# auxDaqUnitBottom2022.net
KiCad netlist of a schematic drawn in EAGLE
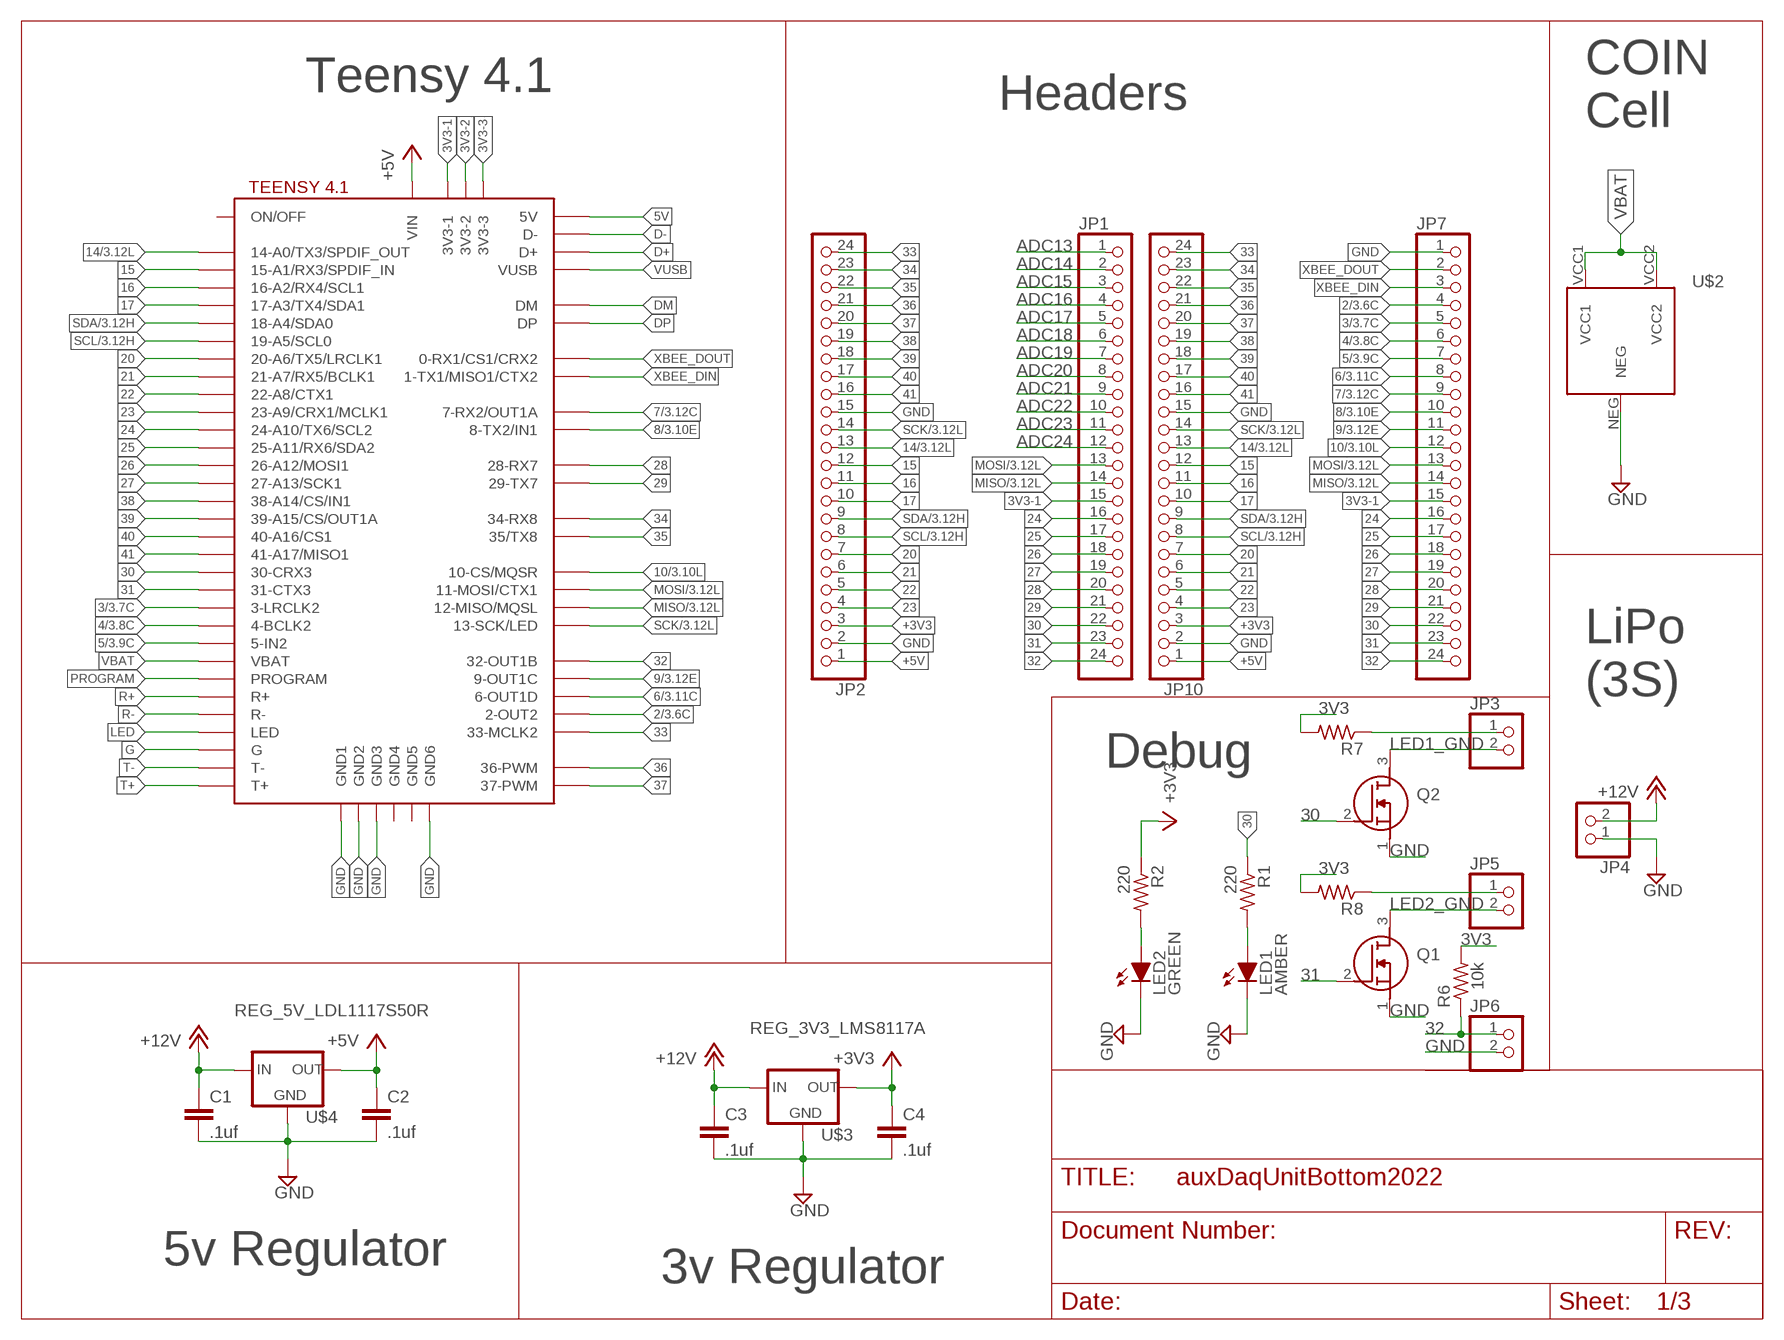
[diagram p0: schematic, sheet 1]
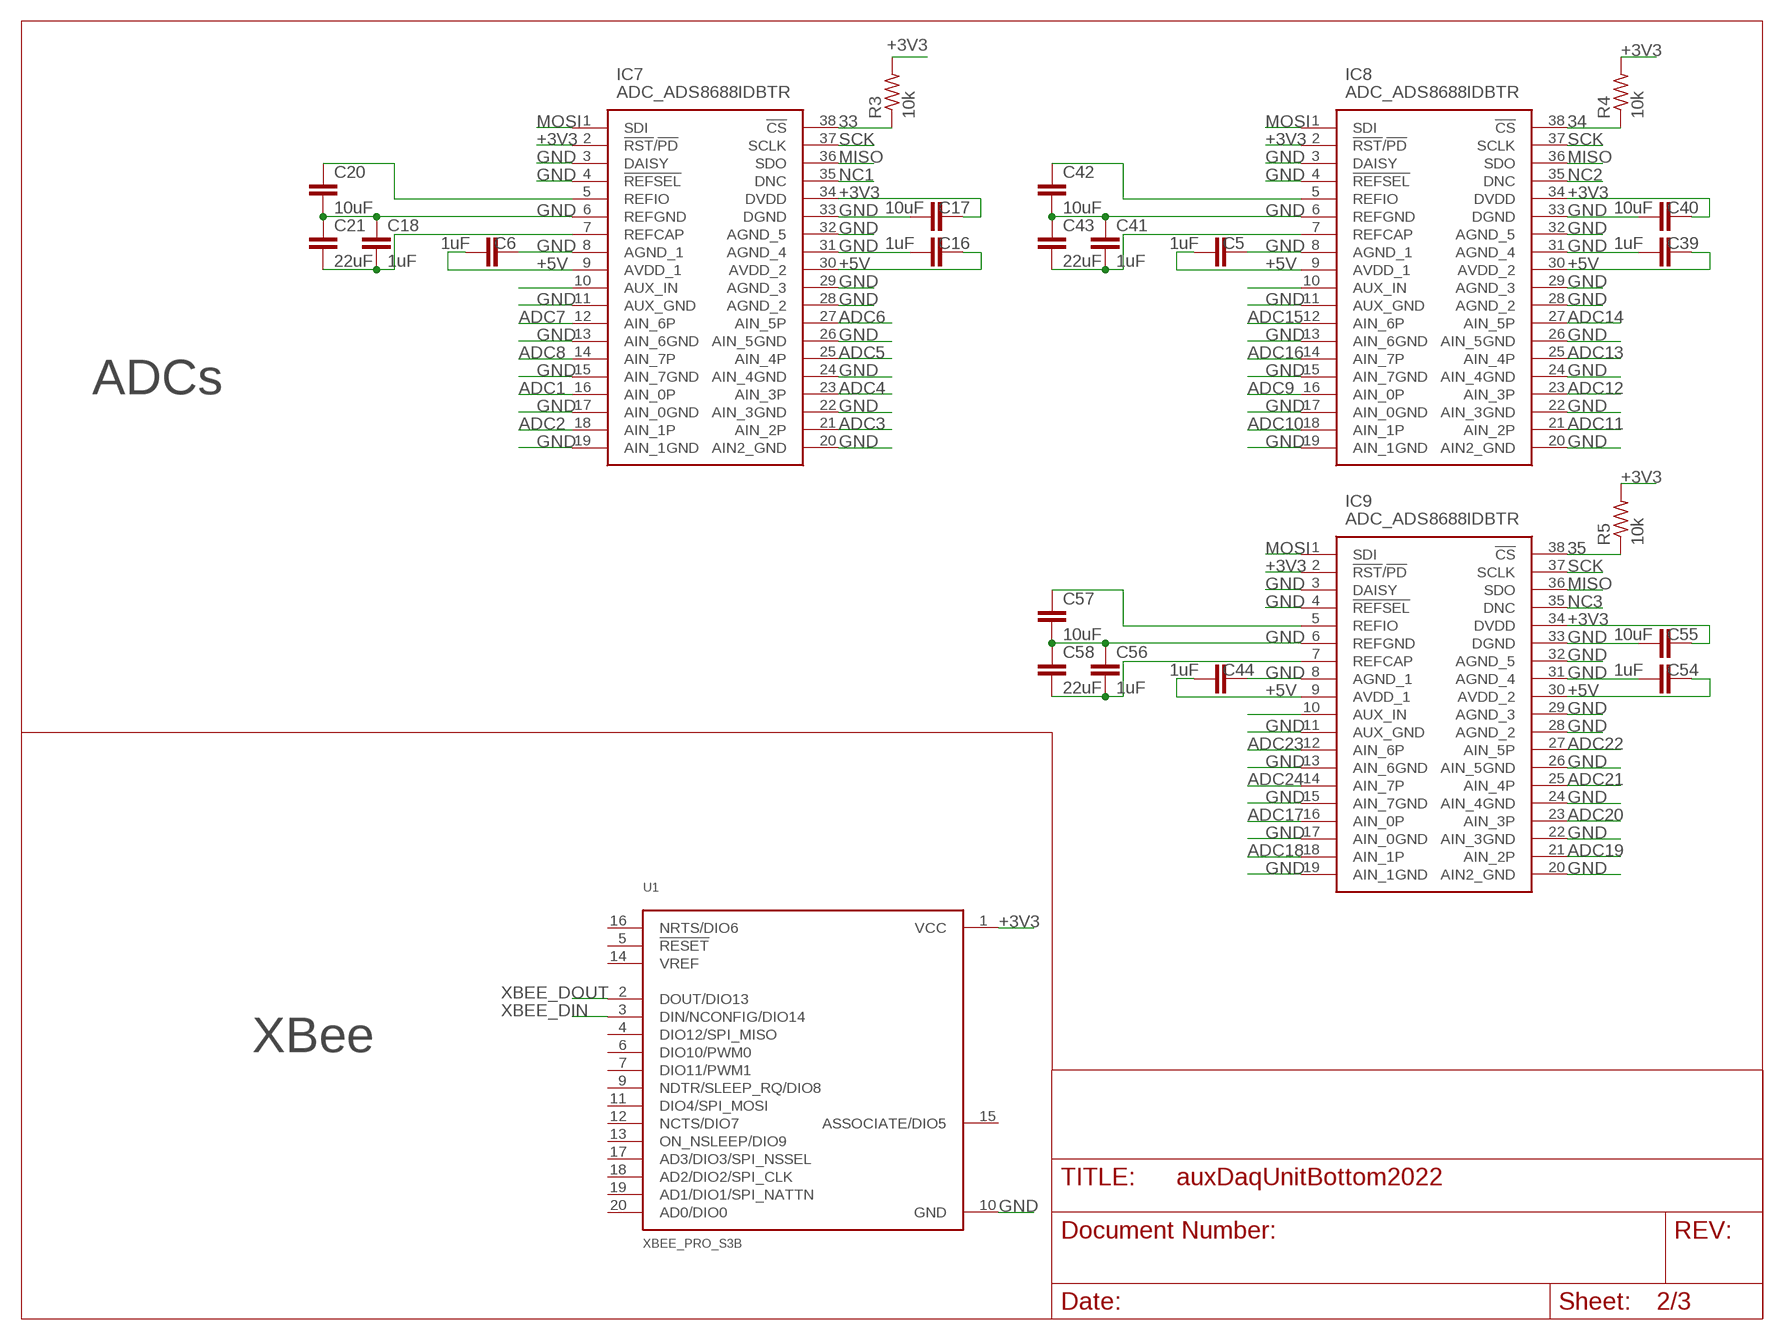
[diagram p1: schematic, sheet 2]
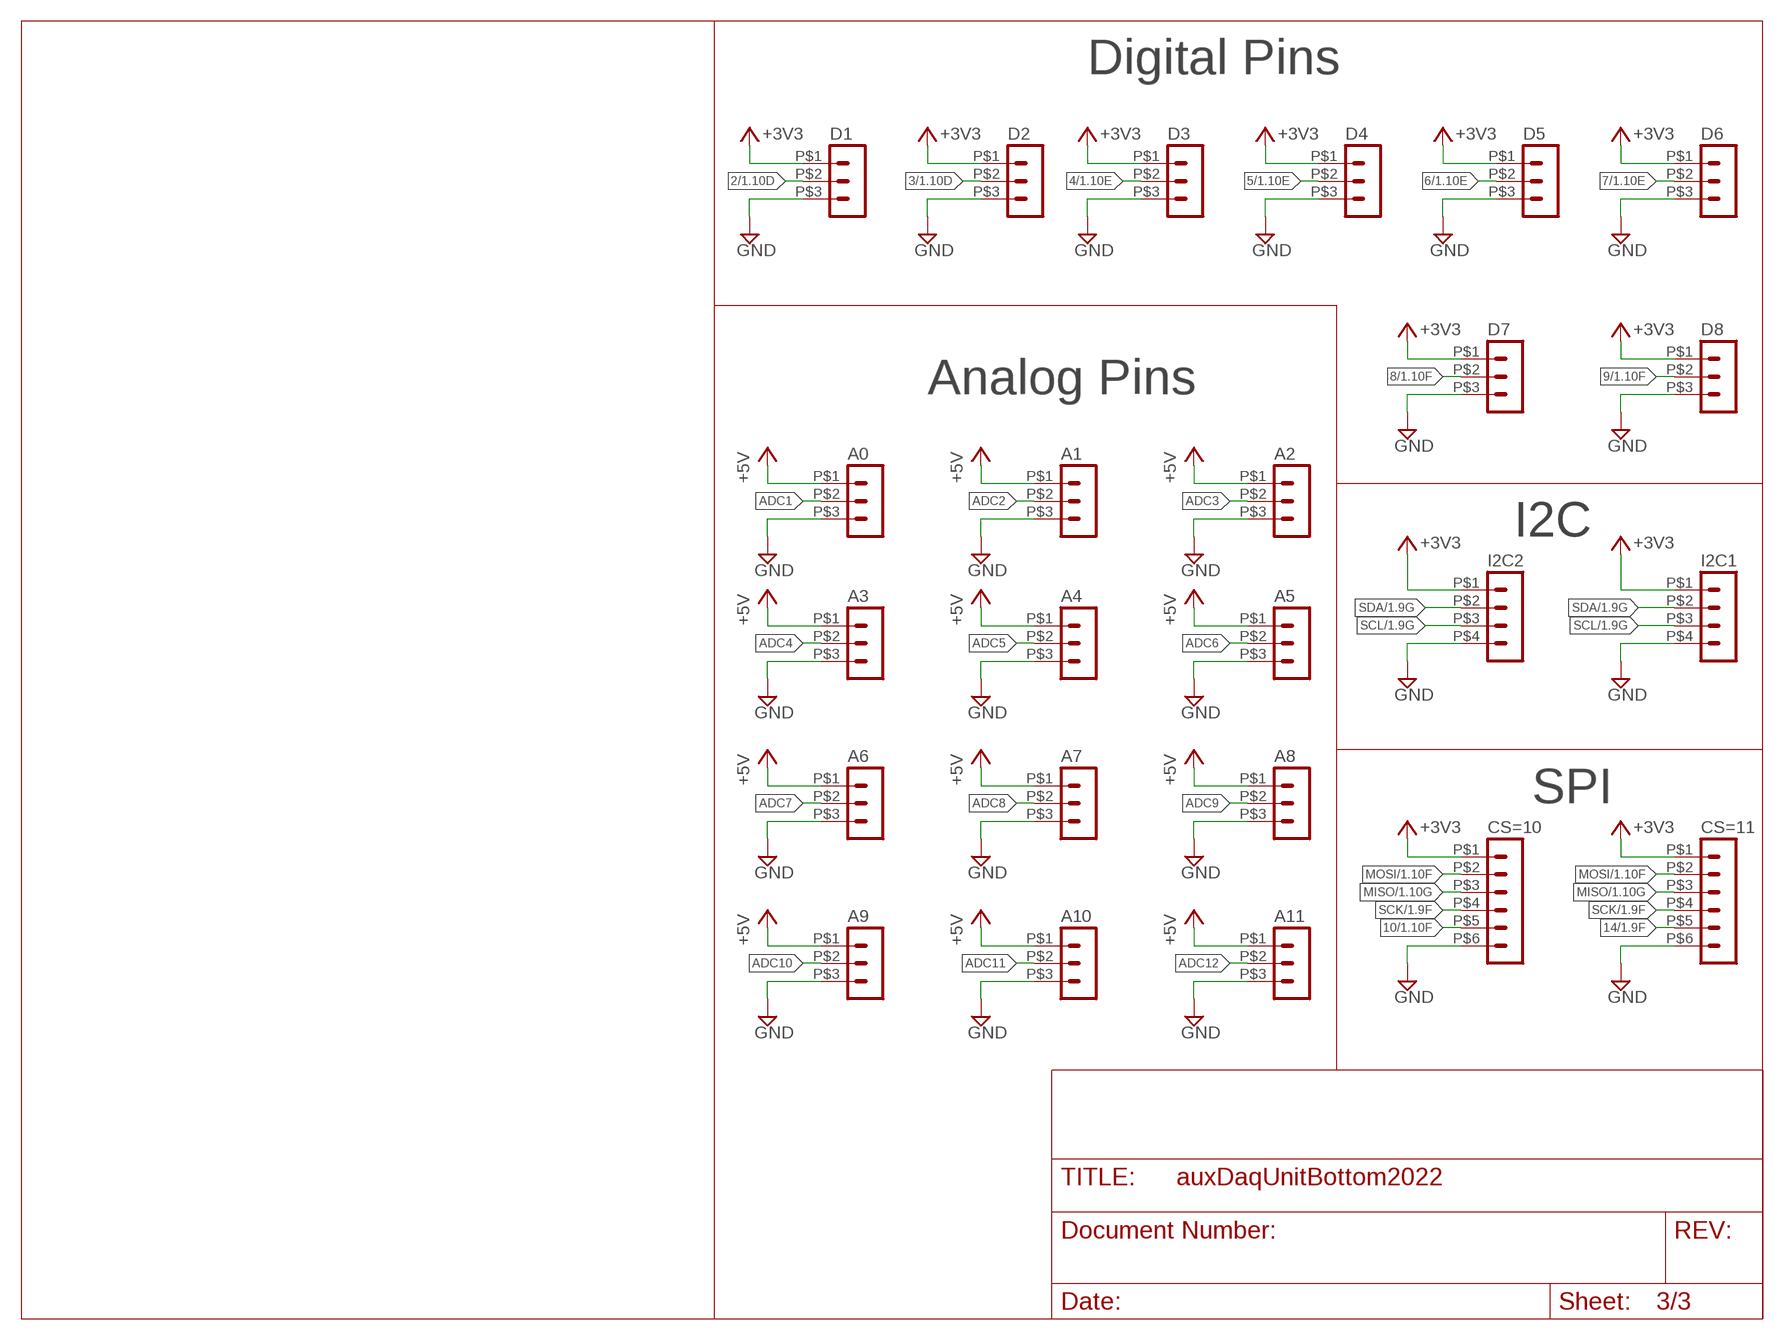
[diagram p2: schematic, sheet 3]

(export (version "E")
  (design (tool "Eeschema 10.0.6"))
  (components
    (comp (ref "C1")
      (value ".1uf")
      (footprint "eagle-import:C0603")
      (libsource (lib "eagle-import") (part "CAP_SMDC0603"))
    )
    (comp (ref "C2")
      (value ".1uf")
      (footprint "eagle-import:C0603")
      (libsource (lib "eagle-import") (part "CAP_SMDC0603"))
    )
    (comp (ref "C3")
      (value ".1uf")
      (footprint "eagle-import:C0603")
      (libsource (lib "eagle-import") (part "CAP_SMDC0603"))
    )
    (comp (ref "C4")
      (value ".1uf")
      (footprint "eagle-import:C0603")
      (libsource (lib "eagle-import") (part "CAP_SMDC0603"))
    )
    (comp (ref "JP1")
      (value "PINHD-1X24")
      (footprint "eagle-import:1X24")
      (libsource (lib "eagle-import") (part "PINHD-1X24"))
    )
    (comp (ref "JP2")
      (value "PINHD-1X24")
      (footprint "eagle-import:1X24")
      (libsource (lib "eagle-import") (part "PINHD-1X24"))
    )
    (comp (ref "JP3")
      (value "PINHD-1X2")
      (footprint "eagle-import:1X02")
      (libsource (lib "eagle-import") (part "PINHD-1X2"))
    )
    (comp (ref "JP4")
      (value "PINHD-1X2")
      (footprint "eagle-import:1X02")
      (libsource (lib "eagle-import") (part "PINHD-1X2"))
    )
    (comp (ref "JP5")
      (value "PINHD-1X2")
      (footprint "eagle-import:1X02")
      (libsource (lib "eagle-import") (part "PINHD-1X2"))
    )
    (comp (ref "JP6")
      (value "PINHD-1X2")
      (footprint "eagle-import:1X02")
      (libsource (lib "eagle-import") (part "PINHD-1X2"))
    )
    (comp (ref "JP7")
      (value "PINHD-1X24")
      (footprint "eagle-import:1X24")
      (libsource (lib "eagle-import") (part "PINHD-1X24"))
    )
    (comp (ref "JP10")
      (value "PINHD-1X24")
      (footprint "eagle-import:1X24")
      (libsource (lib "eagle-import") (part "PINHD-1X24"))
    )
    (comp (ref "LED1")
      (value "AMBER")
      (footprint "eagle-import:LED-603")
      (libsource (lib "eagle-import") (part "LED-0603"))
    )
    (comp (ref "LED2")
      (value "GREEN")
      (footprint "eagle-import:LED-603")
      (libsource (lib "eagle-import") (part "LED-0603"))
    )
    (comp (ref "Q1")
      (value "MOSFET_N-TYPE_RK7002BMT116")
      (footprint "eagle-import:BSS64AHZGT116")
      (fields
        (field (name "MANUFACTURER_PART_NUMBER") "RK7002BMT116")
        (field (name "MOUSER_PART_NUMBER") "755-RK7002BMT116")
      )
      (libsource (lib "eagle-import") (part "MOSFET_N-TYPE_RK7002BMT116"))
    )
    (comp (ref "Q2")
      (value "MOSFET_N-TYPE_RK7002BMT116")
      (footprint "eagle-import:BSS64AHZGT116")
      (fields
        (field (name "MANUFACTURER_PART_NUMBER") "RK7002BMT116")
        (field (name "MOUSER_PART_NUMBER") "755-RK7002BMT116")
      )
      (libsource (lib "eagle-import") (part "MOSFET_N-TYPE_RK7002BMT116"))
    )
    (comp (ref "R1")
      (value "220")
      (footprint "eagle-import:R0603")
      (libsource (lib "eagle-import") (part "RES_SMDR0603"))
    )
    (comp (ref "R2")
      (value "220")
      (footprint "eagle-import:R0603")
      (libsource (lib "eagle-import") (part "RES_SMDR0603"))
    )
    (comp (ref "R6")
      (value "10k")
      (footprint "eagle-import:R0603")
      (libsource (lib "eagle-import") (part "RES_SMDR0603"))
    )
    (comp (ref "R7")
      (value "RES_SMDR0603")
      (footprint "eagle-import:R0603")
      (libsource (lib "eagle-import") (part "RES_SMDR0603"))
    )
    (comp (ref "R8")
      (value "RES_SMDR0603")
      (footprint "eagle-import:R0603")
      (libsource (lib "eagle-import") (part "RES_SMDR0603"))
    )
    (comp (ref "U$1")
      (value "TEENSY41")
      (footprint "eagle-import:TEENSY41")
      (libsource (lib "eagle-import") (part "TEENSY41"))
    )
    (comp (ref "U$2")
      (value "KEYSTONE3035")
      (footprint "eagle-import:KEYSTONE3035")
      (libsource (lib "eagle-import") (part "KEYSTONE3035"))
    )
    (comp (ref "U$3")
      (value "REG_3V3_LMS8117A")
      (footprint "eagle-import:SOT223")
      (libsource (lib "eagle-import") (part "REG_3V3_LMS8117A"))
    )
    (comp (ref "U$4")
      (value "REG_5V_LDL1117S50R")
      (footprint "eagle-import:SOT230P700X180-4N")
      (libsource (lib "eagle-import") (part "REG_5V_LDL1117S50R"))
    )
    (comp (ref "C5")
      (value "1uF")
      (footprint "eagle-import:C0603")
      (libsource (lib "eagle-import") (part "CAP_SMDC0603"))
    )
    (comp (ref "C6")
      (value "1uF")
      (footprint "eagle-import:C0603")
      (libsource (lib "eagle-import") (part "CAP_SMDC0603"))
    )
    (comp (ref "C16")
      (value "1uF")
      (footprint "eagle-import:C0603")
      (libsource (lib "eagle-import") (part "CAP_SMDC0603"))
    )
    (comp (ref "C17")
      (value "10uF")
      (footprint "eagle-import:C0603")
      (libsource (lib "eagle-import") (part "CAP_SMDC0603"))
    )
    (comp (ref "C18")
      (value "1uF")
      (footprint "eagle-import:C0603")
      (libsource (lib "eagle-import") (part "CAP_SMDC0603"))
    )
    (comp (ref "C20")
      (value "10uF")
      (footprint "eagle-import:C0805")
      (libsource (lib "eagle-import") (part "CAP_SMDC0805"))
    )
    (comp (ref "C21")
      (value "22uF")
      (footprint "eagle-import:C1210")
      (libsource (lib "eagle-import") (part "CAP_SMDC1210"))
    )
    (comp (ref "C39")
      (value "1uF")
      (footprint "eagle-import:C0603")
      (libsource (lib "eagle-import") (part "CAP_SMDC0603"))
    )
    (comp (ref "C40")
      (value "10uF")
      (footprint "eagle-import:C0603")
      (libsource (lib "eagle-import") (part "CAP_SMDC0603"))
    )
    (comp (ref "C41")
      (value "1uF")
      (footprint "eagle-import:C0603")
      (libsource (lib "eagle-import") (part "CAP_SMDC0603"))
    )
    (comp (ref "C42")
      (value "10uF")
      (footprint "eagle-import:C0805")
      (libsource (lib "eagle-import") (part "CAP_SMDC0805"))
    )
    (comp (ref "C43")
      (value "22uF")
      (footprint "eagle-import:C1210")
      (libsource (lib "eagle-import") (part "CAP_SMDC1210"))
    )
    (comp (ref "C44")
      (value "1uF")
      (footprint "eagle-import:C0603")
      (libsource (lib "eagle-import") (part "CAP_SMDC0603"))
    )
    (comp (ref "C54")
      (value "1uF")
      (footprint "eagle-import:C0603")
      (libsource (lib "eagle-import") (part "CAP_SMDC0603"))
    )
    (comp (ref "C55")
      (value "10uF")
      (footprint "eagle-import:C0603")
      (libsource (lib "eagle-import") (part "CAP_SMDC0603"))
    )
    (comp (ref "C56")
      (value "1uF")
      (footprint "eagle-import:C0603")
      (libsource (lib "eagle-import") (part "CAP_SMDC0603"))
    )
    (comp (ref "C57")
      (value "10uF")
      (footprint "eagle-import:C0805")
      (libsource (lib "eagle-import") (part "CAP_SMDC0805"))
    )
    (comp (ref "C58")
      (value "22uF")
      (footprint "eagle-import:C1210")
      (libsource (lib "eagle-import") (part "CAP_SMDC1210"))
    )
    (comp (ref "IC7")
      (value "ADC_ADS8688IDBTR")
      (footprint "eagle-import:SOP50P640X120-38N")
      (fields
        (field (name "ARROW_PART_NUMBER") "ADS8688IDBTR")
        (field (name "MOUSER_PART_NUMBER") "595-ADS8688IDBTR")
      )
      (libsource (lib "eagle-import") (part "ADC_ADS8688IDBTR"))
    )
    (comp (ref "IC8")
      (value "ADC_ADS8688IDBTR")
      (footprint "eagle-import:SOP50P640X120-38N")
      (fields
        (field (name "ARROW_PART_NUMBER") "ADS8688IDBTR")
        (field (name "MOUSER_PART_NUMBER") "595-ADS8688IDBTR")
      )
      (libsource (lib "eagle-import") (part "ADC_ADS8688IDBTR"))
    )
    (comp (ref "IC9")
      (value "ADC_ADS8688IDBTR")
      (footprint "eagle-import:SOP50P640X120-38N")
      (fields
        (field (name "ARROW_PART_NUMBER") "ADS8688IDBTR")
        (field (name "MOUSER_PART_NUMBER") "595-ADS8688IDBTR")
      )
      (libsource (lib "eagle-import") (part "ADC_ADS8688IDBTR"))
    )
    (comp (ref "R3")
      (value "10k")
      (footprint "eagle-import:R0603")
      (libsource (lib "eagle-import") (part "RES_SMDR0603"))
    )
    (comp (ref "R4")
      (value "10k")
      (footprint "eagle-import:R0603")
      (libsource (lib "eagle-import") (part "RES_SMDR0603"))
    )
    (comp (ref "R5")
      (value "10k")
      (footprint "eagle-import:R0603")
      (libsource (lib "eagle-import") (part "RES_SMDR0603"))
    )
    (comp (ref "U1")
      (value "XBEE_PRO_S3B")
      (footprint "eagle-import:XBEE_PRO_S3B")
      (fields
        (field (name "DIGI-KEY_PART_NUMBER") "602-1293-ND")
        (field (name "MF") "Digi International")
        (field (name "MP") "XBP9B-XCST-001")
      )
      (libsource (lib "eagle-import") (part "XBEE_PRO_S3B"))
    )
    (comp (ref "A0")
      (value "HEADER_POS3_43650-0300")
      (footprint "eagle-import:43650-0300")
      (libsource (lib "eagle-import") (part "HEADER_POS3_?43650-0300"))
    )
    (comp (ref "A1")
      (value "HEADER_POS3_43650-0300")
      (footprint "eagle-import:43650-0300")
      (libsource (lib "eagle-import") (part "HEADER_POS3_?43650-0300"))
    )
    (comp (ref "A2")
      (value "HEADER_POS3_43650-0300")
      (footprint "eagle-import:43650-0300")
      (libsource (lib "eagle-import") (part "HEADER_POS3_?43650-0300"))
    )
    (comp (ref "A3")
      (value "HEADER_POS3_43650-0300")
      (footprint "eagle-import:43650-0300")
      (libsource (lib "eagle-import") (part "HEADER_POS3_?43650-0300"))
    )
    (comp (ref "A4")
      (value "HEADER_POS3_43650-0300")
      (footprint "eagle-import:43650-0300")
      (libsource (lib "eagle-import") (part "HEADER_POS3_?43650-0300"))
    )
    (comp (ref "A5")
      (value "HEADER_POS3_43650-0300")
      (footprint "eagle-import:43650-0300")
      (libsource (lib "eagle-import") (part "HEADER_POS3_?43650-0300"))
    )
    (comp (ref "A6")
      (value "HEADER_POS3_43650-0300")
      (footprint "eagle-import:43650-0300")
      (libsource (lib "eagle-import") (part "HEADER_POS3_?43650-0300"))
    )
    (comp (ref "A7")
      (value "HEADER_POS3_43650-0300")
      (footprint "eagle-import:43650-0300")
      (libsource (lib "eagle-import") (part "HEADER_POS3_?43650-0300"))
    )
    (comp (ref "A8")
      (value "HEADER_POS3_43650-0300")
      (footprint "eagle-import:43650-0300")
      (libsource (lib "eagle-import") (part "HEADER_POS3_?43650-0300"))
    )
    (comp (ref "A9")
      (value "HEADER_POS3_43650-0300")
      (footprint "eagle-import:43650-0300")
      (libsource (lib "eagle-import") (part "HEADER_POS3_?43650-0300"))
    )
    (comp (ref "A10")
      (value "HEADER_POS3_43650-0300")
      (footprint "eagle-import:43650-0300")
      (libsource (lib "eagle-import") (part "HEADER_POS3_?43650-0300"))
    )
    (comp (ref "A11")
      (value "HEADER_POS3_43650-0300")
      (footprint "eagle-import:43650-0300")
      (libsource (lib "eagle-import") (part "HEADER_POS3_?43650-0300"))
    )
    (comp (ref "CS=10")
      (value "HEADER_POS6_43045-0600")
      (footprint "eagle-import:43045-0600")
      (libsource (lib "eagle-import") (part "HEADER_POS6_?43045-0600"))
    )
    (comp (ref "CS=11")
      (value "HEADER_POS6_43045-0600")
      (footprint "eagle-import:43045-0600")
      (libsource (lib "eagle-import") (part "HEADER_POS6_?43045-0600"))
    )
    (comp (ref "D1")
      (value "HEADER_POS3_43650-0300")
      (footprint "eagle-import:43650-0300")
      (libsource (lib "eagle-import") (part "HEADER_POS3_?43650-0300"))
    )
    (comp (ref "D2")
      (value "HEADER_POS3_43650-0300")
      (footprint "eagle-import:43650-0300")
      (libsource (lib "eagle-import") (part "HEADER_POS3_?43650-0300"))
    )
    (comp (ref "D3")
      (value "HEADER_POS3_43650-0300")
      (footprint "eagle-import:43650-0300")
      (libsource (lib "eagle-import") (part "HEADER_POS3_?43650-0300"))
    )
    (comp (ref "D4")
      (value "HEADER_POS3_43650-0300")
      (footprint "eagle-import:43650-0300")
      (libsource (lib "eagle-import") (part "HEADER_POS3_?43650-0300"))
    )
    (comp (ref "D5")
      (value "HEADER_POS3_43650-0300")
      (footprint "eagle-import:43650-0300")
      (libsource (lib "eagle-import") (part "HEADER_POS3_?43650-0300"))
    )
    (comp (ref "D6")
      (value "HEADER_POS3_43650-0300")
      (footprint "eagle-import:43650-0300")
      (libsource (lib "eagle-import") (part "HEADER_POS3_?43650-0300"))
    )
    (comp (ref "D7")
      (value "HEADER_POS3_43650-0300")
      (footprint "eagle-import:43650-0300")
      (libsource (lib "eagle-import") (part "HEADER_POS3_?43650-0300"))
    )
    (comp (ref "D8")
      (value "HEADER_POS3_43650-0300")
      (footprint "eagle-import:43650-0300")
      (libsource (lib "eagle-import") (part "HEADER_POS3_?43650-0300"))
    )
    (comp (ref "I2C1")
      (value "HEADER_POS4_43045-0401")
      (footprint "eagle-import:43045-0400")
      (libsource (lib "eagle-import") (part "HEADER_POS4_?43045-0401"))
    )
    (comp (ref "I2C2")
      (value "HEADER_POS4_43045-0401")
      (footprint "eagle-import:43045-0400")
      (libsource (lib "eagle-import") (part "HEADER_POS4_?43045-0401"))
    )
  )
  (nets
    (net (code "1") (name "+3V3") (class "Default")
      (node (ref "C17") (pin "1") (pinfunction "1_1") (pintype "passive"))
      (node (ref "C4") (pin "1") (pinfunction "1_1") (pintype "passive"))
      (node (ref "C40") (pin "1") (pinfunction "1_1") (pintype "passive"))
      (node (ref "C55") (pin "1") (pinfunction "1_1") (pintype "passive"))
      (node (ref "CS=10") (pin "P$1") (pinfunction "1_P$1") (pintype "passive"))
      (node (ref "CS=11") (pin "P$1") (pinfunction "1_P$1") (pintype "passive"))
      (node (ref "D1") (pin "P$1") (pinfunction "1_P$1") (pintype "passive"))
      (node (ref "D2") (pin "P$1") (pinfunction "1_P$1") (pintype "passive"))
      (node (ref "D3") (pin "P$1") (pinfunction "1_P$1") (pintype "passive"))
      (node (ref "D4") (pin "P$1") (pinfunction "1_P$1") (pintype "passive"))
      (node (ref "D5") (pin "P$1") (pinfunction "1_P$1") (pintype "passive"))
      (node (ref "D6") (pin "P$1") (pinfunction "1_P$1") (pintype "passive"))
      (node (ref "D7") (pin "P$1") (pinfunction "1_P$1") (pintype "passive"))
      (node (ref "D8") (pin "P$1") (pinfunction "1_P$1") (pintype "passive"))
      (node (ref "I2C1") (pin "P$1") (pinfunction "1_P$1") (pintype "passive"))
      (node (ref "I2C2") (pin "P$1") (pinfunction "1_P$1") (pintype "passive"))
      (node (ref "IC7") (pin "2") (pinfunction "~{RST}/~{PD}_2") (pintype "bidirectional"))
      (node (ref "IC7") (pin "34") (pinfunction "DVDD_34") (pintype "bidirectional"))
      (node (ref "IC8") (pin "2") (pinfunction "~{RST}/~{PD}_2") (pintype "bidirectional"))
      (node (ref "IC8") (pin "34") (pinfunction "DVDD_34") (pintype "bidirectional"))
      (node (ref "IC9") (pin "2") (pinfunction "~{RST}/~{PD}_2") (pintype "bidirectional"))
      (node (ref "IC9") (pin "34") (pinfunction "DVDD_34") (pintype "bidirectional"))
      (node (ref "JP10") (pin "3") (pinfunction "3_3") (pintype "passive"))
      (node (ref "JP2") (pin "3") (pinfunction "3_3") (pintype "passive"))
      (node (ref "R2") (pin "1") (pinfunction "1_1") (pintype "passive"))
      (node (ref "R3") (pin "2") (pinfunction "2_2") (pintype "passive"))
      (node (ref "R4") (pin "2") (pinfunction "2_2") (pintype "passive"))
      (node (ref "R5") (pin "2") (pinfunction "2_2") (pintype "passive"))
      (node (ref "U$3") (pin "2") (pinfunction "OUT_2") (pintype "output"))
      (node (ref "U$3") (pin "4") (pinfunction "OUT_4") (pintype "output"))
      (node (ref "U1") (pin "1") (pinfunction "VCC_1") (pintype "power_in"))
    )
    (net (code "2") (name "+5V") (class "Default")
      (node (ref "A0") (pin "P$1") (pinfunction "1_P$1") (pintype "passive"))
      (node (ref "A1") (pin "P$1") (pinfunction "1_P$1") (pintype "passive"))
      (node (ref "A10") (pin "P$1") (pinfunction "1_P$1") (pintype "passive"))
      (node (ref "A11") (pin "P$1") (pinfunction "1_P$1") (pintype "passive"))
      (node (ref "A2") (pin "P$1") (pinfunction "1_P$1") (pintype "passive"))
      (node (ref "A3") (pin "P$1") (pinfunction "1_P$1") (pintype "passive"))
      (node (ref "A4") (pin "P$1") (pinfunction "1_P$1") (pintype "passive"))
      (node (ref "A5") (pin "P$1") (pinfunction "1_P$1") (pintype "passive"))
      (node (ref "A6") (pin "P$1") (pinfunction "1_P$1") (pintype "passive"))
      (node (ref "A7") (pin "P$1") (pinfunction "1_P$1") (pintype "passive"))
      (node (ref "A8") (pin "P$1") (pinfunction "1_P$1") (pintype "passive"))
      (node (ref "A9") (pin "P$1") (pinfunction "1_P$1") (pintype "passive"))
      (node (ref "C16") (pin "1") (pinfunction "1_1") (pintype "passive"))
      (node (ref "C2") (pin "1") (pinfunction "1_1") (pintype "passive"))
      (node (ref "C39") (pin "1") (pinfunction "1_1") (pintype "passive"))
      (node (ref "C44") (pin "2") (pinfunction "2_2") (pintype "passive"))
      (node (ref "C5") (pin "2") (pinfunction "2_2") (pintype "passive"))
      (node (ref "C54") (pin "1") (pinfunction "1_1") (pintype "passive"))
      (node (ref "C6") (pin "2") (pinfunction "2_2") (pintype "passive"))
      (node (ref "IC7") (pin "30") (pinfunction "AVDD_2_30") (pintype "bidirectional"))
      (node (ref "IC7") (pin "9") (pinfunction "AVDD_1_9") (pintype "bidirectional"))
      (node (ref "IC8") (pin "30") (pinfunction "AVDD_2_30") (pintype "bidirectional"))
      (node (ref "IC8") (pin "9") (pinfunction "AVDD_1_9") (pintype "bidirectional"))
      (node (ref "IC9") (pin "30") (pinfunction "AVDD_2_30") (pintype "bidirectional"))
      (node (ref "IC9") (pin "9") (pinfunction "AVDD_1_9") (pintype "bidirectional"))
      (node (ref "JP10") (pin "1") (pinfunction "1_1") (pintype "passive"))
      (node (ref "JP2") (pin "1") (pinfunction "1_1") (pintype "passive"))
      (node (ref "U$1") (pin "VIN") (pinfunction "VIN_VIN") (pintype "bidirectional"))
      (node (ref "U$4") (pin "2") (pinfunction "OUT_2") (pintype "output"))
      (node (ref "U$4") (pin "4") (pinfunction "OUT_4") (pintype "output"))
    )
    (net (code "3") (name "+12V") (class "Default")
      (node (ref "C1") (pin "1") (pinfunction "1_1") (pintype "passive"))
      (node (ref "C3") (pin "1") (pinfunction "1_1") (pintype "passive"))
      (node (ref "JP4") (pin "2") (pinfunction "2_2") (pintype "passive"))
      (node (ref "U$3") (pin "3") (pinfunction "IN_3") (pintype "input"))
      (node (ref "U$4") (pin "3") (pinfunction "IN_3") (pintype "input"))
    )
    (net (code "4") (name "2") (class "Default")
      (node (ref "D1") (pin "P$2") (pinfunction "2_P$2") (pintype "passive"))
      (node (ref "JP7") (pin "4") (pinfunction "4_4") (pintype "passive"))
      (node (ref "U$1") (pin "2-OUT2") (pinfunction "2-OUT2_2-OUT2") (pintype "bidirectional"))
    )
    (net (code "5") (name "3") (class "Default")
      (node (ref "D2") (pin "P$2") (pinfunction "2_P$2") (pintype "passive"))
      (node (ref "JP7") (pin "5") (pinfunction "5_5") (pintype "passive"))
      (node (ref "U$1") (pin "3-LRCLK2") (pinfunction "3-LRCLK2_3-LRCLK2") (pintype "bidirectional"))
    )
    (net (code "6") (name "3V3") (class "Default")
      (node (ref "R6") (pin "2") (pinfunction "2_2") (pintype "passive"))
      (node (ref "R7") (pin "2") (pinfunction "2_2") (pintype "passive"))
      (node (ref "R8") (pin "2") (pinfunction "2_2") (pintype "passive"))
    )
    (net (code "7") (name "3V3-1") (class "Default")
      (node (ref "JP1") (pin "15") (pinfunction "15_15") (pintype "passive"))
      (node (ref "JP7") (pin "15") (pinfunction "15_15") (pintype "passive"))
      (node (ref "U$1") (pin "3V3-1") (pinfunction "3V3-1_3V3-1") (pintype "bidirectional"))
    )
    (net (code "8") (name "3V3-2") (class "Default")
      (node (ref "U$1") (pin "3V3-2") (pinfunction "3V3-2_3V3-2") (pintype "bidirectional"))
    )
    (net (code "9") (name "3V3-3") (class "Default")
      (node (ref "U$1") (pin "3V3-3") (pinfunction "3V3-3_3V3-3") (pintype "bidirectional"))
    )
    (net (code "10") (name "4") (class "Default")
      (node (ref "D3") (pin "P$2") (pinfunction "2_P$2") (pintype "passive"))
      (node (ref "JP7") (pin "6") (pinfunction "6_6") (pintype "passive"))
      (node (ref "U$1") (pin "4-BCLK2") (pinfunction "4-BCLK2_4-BCLK2") (pintype "bidirectional"))
    )
    (net (code "11") (name "5") (class "Default")
      (node (ref "D4") (pin "P$2") (pinfunction "2_P$2") (pintype "passive"))
      (node (ref "JP7") (pin "7") (pinfunction "7_7") (pintype "passive"))
      (node (ref "U$1") (pin "5-IN2") (pinfunction "5-IN2_5-IN2") (pintype "bidirectional"))
    )
    (net (code "12") (name "5V") (class "Default")
      (node (ref "U$1") (pin "+5V") (pinfunction "5V_+5V") (pintype "bidirectional"))
    )
    (net (code "13") (name "6") (class "Default")
      (node (ref "D5") (pin "P$2") (pinfunction "2_P$2") (pintype "passive"))
      (node (ref "JP7") (pin "8") (pinfunction "8_8") (pintype "passive"))
      (node (ref "U$1") (pin "6-OUT1D") (pinfunction "6-OUT1D_6-OUT1D") (pintype "bidirectional"))
    )
    (net (code "14") (name "7") (class "Default")
      (node (ref "D6") (pin "P$2") (pinfunction "2_P$2") (pintype "passive"))
      (node (ref "JP7") (pin "9") (pinfunction "9_9") (pintype "passive"))
      (node (ref "U$1") (pin "7-RX2/OUT1A") (pinfunction "7-RX2/OUT1A_7-RX2/OUT1A") (pintype "bidirectional"))
    )
    (net (code "15") (name "8") (class "Default")
      (node (ref "D7") (pin "P$2") (pinfunction "2_P$2") (pintype "passive"))
      (node (ref "JP7") (pin "10") (pinfunction "10_10") (pintype "passive"))
      (node (ref "U$1") (pin "8-TX2/IN2") (pinfunction "8-TX2/IN1_8-TX2/IN2") (pintype "bidirectional"))
    )
    (net (code "16") (name "9") (class "Default")
      (node (ref "D8") (pin "P$2") (pinfunction "2_P$2") (pintype "passive"))
      (node (ref "JP7") (pin "11") (pinfunction "11_11") (pintype "passive"))
      (node (ref "U$1") (pin "9-OUT1C") (pinfunction "9-OUT1C_9-OUT1C") (pintype "bidirectional"))
    )
    (net (code "17") (name "10") (class "Default")
      (node (ref "CS=10") (pin "P$5") (pinfunction "5_P$5") (pintype "passive"))
      (node (ref "JP7") (pin "12") (pinfunction "12_12") (pintype "passive"))
      (node (ref "U$1") (pin "10-CS\\MQSR") (pinfunction "10-CS/MQSR_10-CS\\MQSR") (pintype "bidirectional"))
    )
    (net (code "18") (name "14") (class "Default")
      (node (ref "CS=11") (pin "P$5") (pinfunction "5_P$5") (pintype "passive"))
      (node (ref "JP10") (pin "13") (pinfunction "13_13") (pintype "passive"))
      (node (ref "JP2") (pin "13") (pinfunction "13_13") (pintype "passive"))
      (node (ref "U$1") (pin "14-A0/TX3/SPDIF_OUT") (pinfunction "14-A0/TX3/SPDIF_OUT_14-A0/TX3/SPDIF_OUT") (pintype "bidirectional"))
    )
    (net (code "19") (name "15") (class "Default")
      (node (ref "JP10") (pin "12") (pinfunction "12_12") (pintype "passive"))
      (node (ref "JP2") (pin "12") (pinfunction "12_12") (pintype "passive"))
      (node (ref "U$1") (pin "15-A1/RX3/SPDIF_IN") (pinfunction "15-A1/RX3/SPDIF_IN_15-A1/RX3/SPDIF_IN") (pintype "bidirectional"))
    )
    (net (code "20") (name "16") (class "Default")
      (node (ref "JP10") (pin "11") (pinfunction "11_11") (pintype "passive"))
      (node (ref "JP2") (pin "11") (pinfunction "11_11") (pintype "passive"))
      (node (ref "U$1") (pin "16-A2/RX4/SCL1") (pinfunction "16-A2/RX4/SCL1_16-A2/RX4/SCL1") (pintype "bidirectional"))
    )
    (net (code "21") (name "17") (class "Default")
      (node (ref "JP10") (pin "10") (pinfunction "10_10") (pintype "passive"))
      (node (ref "JP2") (pin "10") (pinfunction "10_10") (pintype "passive"))
      (node (ref "U$1") (pin "17-A3/TX4/SDA1") (pinfunction "17-A3/TX4/SDA1_17-A3/TX4/SDA1") (pintype "bidirectional"))
    )
    (net (code "22") (name "20") (class "Default")
      (node (ref "JP10") (pin "7") (pinfunction "7_7") (pintype "passive"))
      (node (ref "JP2") (pin "7") (pinfunction "7_7") (pintype "passive"))
      (node (ref "U$1") (pin "20-A6/TX5/LRCLK1") (pinfunction "20-A6/TX5/LRCLK1_20-A6/TX5/LRCLK1") (pintype "bidirectional"))
    )
    (net (code "23") (name "21") (class "Default")
      (node (ref "JP10") (pin "6") (pinfunction "6_6") (pintype "passive"))
      (node (ref "JP2") (pin "6") (pinfunction "6_6") (pintype "passive"))
      (node (ref "U$1") (pin "21-A7/RX5/BCLK1") (pinfunction "21-A7/RX5/BCLK1_21-A7/RX5/BCLK1") (pintype "bidirectional"))
    )
    (net (code "24") (name "22") (class "Default")
      (node (ref "JP10") (pin "5") (pinfunction "5_5") (pintype "passive"))
      (node (ref "JP2") (pin "5") (pinfunction "5_5") (pintype "passive"))
      (node (ref "U$1") (pin "22-A8/CTX1") (pinfunction "22-A8/CTX1_22-A8/CTX1") (pintype "bidirectional"))
    )
    (net (code "25") (name "23") (class "Default")
      (node (ref "JP10") (pin "4") (pinfunction "4_4") (pintype "passive"))
      (node (ref "JP2") (pin "4") (pinfunction "4_4") (pintype "passive"))
      (node (ref "U$1") (pin "23-A9/CRX1/MCLK1") (pinfunction "23-A9/CRX1/MCLK1_23-A9/CRX1/MCLK1") (pintype "bidirectional"))
    )
    (net (code "26") (name "24") (class "Default")
      (node (ref "JP1") (pin "16") (pinfunction "16_16") (pintype "passive"))
      (node (ref "JP7") (pin "16") (pinfunction "16_16") (pintype "passive"))
      (node (ref "U$1") (pin "24-A10/TX6/SCL2") (pinfunction "24-A10/TX6/SCL2_24-A10/TX6/SCL2") (pintype "bidirectional"))
    )
    (net (code "27") (name "25") (class "Default")
      (node (ref "JP1") (pin "17") (pinfunction "17_17") (pintype "passive"))
      (node (ref "JP7") (pin "17") (pinfunction "17_17") (pintype "passive"))
      (node (ref "U$1") (pin "25-A11/RX6/SDA2") (pinfunction "25-A11/RX6/SDA2_25-A11/RX6/SDA2") (pintype "bidirectional"))
    )
    (net (code "28") (name "26") (class "Default")
      (node (ref "JP1") (pin "18") (pinfunction "18_18") (pintype "passive"))
      (node (ref "JP7") (pin "18") (pinfunction "18_18") (pintype "passive"))
      (node (ref "U$1") (pin "26-A12/MOSI1") (pinfunction "26-A12/MOSI1_26-A12/MOSI1") (pintype "bidirectional"))
    )
    (net (code "29") (name "27") (class "Default")
      (node (ref "JP1") (pin "19") (pinfunction "19_19") (pintype "passive"))
      (node (ref "JP7") (pin "19") (pinfunction "19_19") (pintype "passive"))
      (node (ref "U$1") (pin "27-A13/SCK1") (pinfunction "27-A13/SCK1_27-A13/SCK1") (pintype "bidirectional"))
    )
    (net (code "30") (name "28") (class "Default")
      (node (ref "JP1") (pin "20") (pinfunction "20_20") (pintype "passive"))
      (node (ref "JP7") (pin "20") (pinfunction "20_20") (pintype "passive"))
      (node (ref "U$1") (pin "28-RX7") (pinfunction "28-RX7_28-RX7") (pintype "bidirectional"))
    )
    (net (code "31") (name "29") (class "Default")
      (node (ref "JP1") (pin "21") (pinfunction "21_21") (pintype "passive"))
      (node (ref "JP7") (pin "21") (pinfunction "21_21") (pintype "passive"))
      (node (ref "U$1") (pin "29-TX7") (pinfunction "29-TX7_29-TX7") (pintype "bidirectional"))
    )
    (net (code "32") (name "30") (class "Default")
      (node (ref "JP1") (pin "22") (pinfunction "22_22") (pintype "passive"))
      (node (ref "JP7") (pin "22") (pinfunction "22_22") (pintype "passive"))
      (node (ref "Q2") (pin "2") (pinfunction "G_2") (pintype "bidirectional"))
      (node (ref "R1") (pin "1") (pinfunction "1_1") (pintype "passive"))
      (node (ref "U$1") (pin "30-CRX3") (pinfunction "30-CRX3_30-CRX3") (pintype "bidirectional"))
    )
    (net (code "33") (name "31") (class "Default")
      (node (ref "JP1") (pin "23") (pinfunction "23_23") (pintype "passive"))
      (node (ref "JP7") (pin "23") (pinfunction "23_23") (pintype "passive"))
      (node (ref "Q1") (pin "2") (pinfunction "G_2") (pintype "bidirectional"))
      (node (ref "U$1") (pin "31-CTX3") (pinfunction "31-CTX3_31-CTX3") (pintype "bidirectional"))
    )
    (net (code "34") (name "32") (class "Default")
      (node (ref "JP1") (pin "24") (pinfunction "24_24") (pintype "passive"))
      (node (ref "JP6") (pin "1") (pinfunction "1_1") (pintype "passive"))
      (node (ref "JP7") (pin "24") (pinfunction "24_24") (pintype "passive"))
      (node (ref "R6") (pin "1") (pinfunction "1_1") (pintype "passive"))
      (node (ref "U$1") (pin "32-OUT1B") (pinfunction "32-OUT1B_32-OUT1B") (pintype "bidirectional"))
    )
    (net (code "35") (name "33") (class "Default")
      (node (ref "IC7") (pin "38") (pinfunction "~{CS}_38") (pintype "bidirectional"))
      (node (ref "JP10") (pin "24") (pinfunction "24_24") (pintype "passive"))
      (node (ref "JP2") (pin "24") (pinfunction "24_24") (pintype "passive"))
      (node (ref "R3") (pin "1") (pinfunction "1_1") (pintype "passive"))
      (node (ref "U$1") (pin "33-MCLK2") (pinfunction "33-MCLK2_33-MCLK2") (pintype "bidirectional"))
    )
    (net (code "36") (name "34") (class "Default")
      (node (ref "IC8") (pin "38") (pinfunction "~{CS}_38") (pintype "bidirectional"))
      (node (ref "JP10") (pin "23") (pinfunction "23_23") (pintype "passive"))
      (node (ref "JP2") (pin "23") (pinfunction "23_23") (pintype "passive"))
      (node (ref "R4") (pin "1") (pinfunction "1_1") (pintype "passive"))
      (node (ref "U$1") (pin "34-RX8") (pinfunction "34-RX8_34-RX8") (pintype "bidirectional"))
    )
    (net (code "37") (name "35") (class "Default")
      (node (ref "IC9") (pin "38") (pinfunction "~{CS}_38") (pintype "bidirectional"))
      (node (ref "JP10") (pin "22") (pinfunction "22_22") (pintype "passive"))
      (node (ref "JP2") (pin "22") (pinfunction "22_22") (pintype "passive"))
      (node (ref "R5") (pin "1") (pinfunction "1_1") (pintype "passive"))
      (node (ref "U$1") (pin "35-TX8") (pinfunction "35/TX8_35-TX8") (pintype "bidirectional"))
    )
    (net (code "38") (name "36") (class "Default")
      (node (ref "JP10") (pin "21") (pinfunction "21_21") (pintype "passive"))
      (node (ref "JP2") (pin "21") (pinfunction "21_21") (pintype "passive"))
      (node (ref "U$1") (pin "36-PWM") (pinfunction "36-PWM_36-PWM") (pintype "bidirectional"))
    )
    (net (code "39") (name "37") (class "Default")
      (node (ref "JP10") (pin "20") (pinfunction "20_20") (pintype "passive"))
      (node (ref "JP2") (pin "20") (pinfunction "20_20") (pintype "passive"))
      (node (ref "U$1") (pin "37-PWM") (pinfunction "37-PWM_37-PWM") (pintype "bidirectional"))
    )
    (net (code "40") (name "38") (class "Default")
      (node (ref "JP10") (pin "19") (pinfunction "19_19") (pintype "passive"))
      (node (ref "JP2") (pin "19") (pinfunction "19_19") (pintype "passive"))
      (node (ref "U$1") (pin "38-A14/CS/IN1") (pinfunction "38-A14/CS/IN1_38-A14/CS/IN1") (pintype "bidirectional"))
    )
    (net (code "41") (name "39") (class "Default")
      (node (ref "JP10") (pin "18") (pinfunction "18_18") (pintype "passive"))
      (node (ref "JP2") (pin "18") (pinfunction "18_18") (pintype "passive"))
      (node (ref "U$1") (pin "39-A15/CS/OUT1A") (pinfunction "39-A15/CS/OUT1A_39-A15/CS/OUT1A") (pintype "bidirectional"))
    )
    (net (code "42") (name "40") (class "Default")
      (node (ref "JP10") (pin "17") (pinfunction "17_17") (pintype "passive"))
      (node (ref "JP2") (pin "17") (pinfunction "17_17") (pintype "passive"))
      (node (ref "U$1") (pin "40-A16/CS1") (pinfunction "40-A16/CS1_40-A16/CS1") (pintype "bidirectional"))
    )
    (net (code "43") (name "41") (class "Default")
      (node (ref "JP10") (pin "16") (pinfunction "16_16") (pintype "passive"))
      (node (ref "JP2") (pin "16") (pinfunction "16_16") (pintype "passive"))
      (node (ref "U$1") (pin "41-A17/MISO1") (pinfunction "41-A17/MISO1_41-A17/MISO1") (pintype "bidirectional"))
    )
    (net (code "44") (name "ADC1") (class "Default")
      (node (ref "A0") (pin "P$2") (pinfunction "2_P$2") (pintype "passive"))
      (node (ref "IC7") (pin "16") (pinfunction "AIN_0P_16") (pintype "bidirectional"))
    )
    (net (code "45") (name "ADC2") (class "Default")
      (node (ref "A1") (pin "P$2") (pinfunction "2_P$2") (pintype "passive"))
      (node (ref "IC7") (pin "18") (pinfunction "AIN_1P_18") (pintype "bidirectional"))
    )
    (net (code "46") (name "ADC3") (class "Default")
      (node (ref "A2") (pin "P$2") (pinfunction "2_P$2") (pintype "passive"))
      (node (ref "IC7") (pin "21") (pinfunction "AIN_2P_21") (pintype "bidirectional"))
    )
    (net (code "47") (name "ADC4") (class "Default")
      (node (ref "A3") (pin "P$2") (pinfunction "2_P$2") (pintype "passive"))
      (node (ref "IC7") (pin "23") (pinfunction "AIN_3P_23") (pintype "bidirectional"))
    )
    (net (code "48") (name "ADC5") (class "Default")
      (node (ref "A4") (pin "P$2") (pinfunction "2_P$2") (pintype "passive"))
      (node (ref "IC7") (pin "25") (pinfunction "AIN_4P_25") (pintype "bidirectional"))
    )
    (net (code "49") (name "ADC6") (class "Default")
      (node (ref "A5") (pin "P$2") (pinfunction "2_P$2") (pintype "passive"))
      (node (ref "IC7") (pin "27") (pinfunction "AIN_5P_27") (pintype "bidirectional"))
    )
    (net (code "50") (name "ADC7") (class "Default")
      (node (ref "A6") (pin "P$2") (pinfunction "2_P$2") (pintype "passive"))
      (node (ref "IC7") (pin "12") (pinfunction "AIN_6P_12") (pintype "bidirectional"))
    )
    (net (code "51") (name "ADC8") (class "Default")
      (node (ref "A7") (pin "P$2") (pinfunction "2_P$2") (pintype "passive"))
      (node (ref "IC7") (pin "14") (pinfunction "AIN_7P_14") (pintype "bidirectional"))
    )
    (net (code "52") (name "ADC9") (class "Default")
      (node (ref "A8") (pin "P$2") (pinfunction "2_P$2") (pintype "passive"))
      (node (ref "IC8") (pin "16") (pinfunction "AIN_0P_16") (pintype "bidirectional"))
    )
    (net (code "53") (name "ADC10") (class "Default")
      (node (ref "A9") (pin "P$2") (pinfunction "2_P$2") (pintype "passive"))
      (node (ref "IC8") (pin "18") (pinfunction "AIN_1P_18") (pintype "bidirectional"))
    )
    (net (code "54") (name "ADC11") (class "Default")
      (node (ref "A10") (pin "P$2") (pinfunction "2_P$2") (pintype "passive"))
      (node (ref "IC8") (pin "21") (pinfunction "AIN_2P_21") (pintype "bidirectional"))
    )
    (net (code "55") (name "ADC12") (class "Default")
      (node (ref "A11") (pin "P$2") (pinfunction "2_P$2") (pintype "passive"))
      (node (ref "IC8") (pin "23") (pinfunction "AIN_3P_23") (pintype "bidirectional"))
    )
    (net (code "56") (name "ADC13") (class "Default")
      (node (ref "IC8") (pin "25") (pinfunction "AIN_4P_25") (pintype "bidirectional"))
      (node (ref "JP1") (pin "1") (pinfunction "1_1") (pintype "passive"))
    )
    (net (code "57") (name "ADC14") (class "Default")
      (node (ref "IC8") (pin "27") (pinfunction "AIN_5P_27") (pintype "bidirectional"))
      (node (ref "JP1") (pin "2") (pinfunction "2_2") (pintype "passive"))
    )
    (net (code "58") (name "ADC15") (class "Default")
      (node (ref "IC8") (pin "12") (pinfunction "AIN_6P_12") (pintype "bidirectional"))
      (node (ref "JP1") (pin "3") (pinfunction "3_3") (pintype "passive"))
    )
    (net (code "59") (name "ADC16") (class "Default")
      (node (ref "IC8") (pin "14") (pinfunction "AIN_7P_14") (pintype "bidirectional"))
      (node (ref "JP1") (pin "4") (pinfunction "4_4") (pintype "passive"))
    )
    (net (code "60") (name "ADC17") (class "Default")
      (node (ref "IC9") (pin "16") (pinfunction "AIN_0P_16") (pintype "bidirectional"))
      (node (ref "JP1") (pin "5") (pinfunction "5_5") (pintype "passive"))
    )
    (net (code "61") (name "ADC18") (class "Default")
      (node (ref "IC9") (pin "18") (pinfunction "AIN_1P_18") (pintype "bidirectional"))
      (node (ref "JP1") (pin "6") (pinfunction "6_6") (pintype "passive"))
    )
    (net (code "62") (name "ADC19") (class "Default")
      (node (ref "IC9") (pin "21") (pinfunction "AIN_2P_21") (pintype "bidirectional"))
      (node (ref "JP1") (pin "7") (pinfunction "7_7") (pintype "passive"))
    )
    (net (code "63") (name "ADC20") (class "Default")
      (node (ref "IC9") (pin "23") (pinfunction "AIN_3P_23") (pintype "bidirectional"))
      (node (ref "JP1") (pin "8") (pinfunction "8_8") (pintype "passive"))
    )
    (net (code "64") (name "ADC21") (class "Default")
      (node (ref "IC9") (pin "25") (pinfunction "AIN_4P_25") (pintype "bidirectional"))
      (node (ref "JP1") (pin "9") (pinfunction "9_9") (pintype "passive"))
    )
    (net (code "65") (name "ADC22") (class "Default")
      (node (ref "IC9") (pin "27") (pinfunction "AIN_5P_27") (pintype "bidirectional"))
      (node (ref "JP1") (pin "10") (pinfunction "10_10") (pintype "passive"))
    )
    (net (code "66") (name "ADC23") (class "Default")
      (node (ref "IC9") (pin "12") (pinfunction "AIN_6P_12") (pintype "bidirectional"))
      (node (ref "JP1") (pin "11") (pinfunction "11_11") (pintype "passive"))
    )
    (net (code "67") (name "ADC24") (class "Default")
      (node (ref "IC9") (pin "14") (pinfunction "AIN_7P_14") (pintype "bidirectional"))
      (node (ref "JP1") (pin "12") (pinfunction "12_12") (pintype "passive"))
    )
    (net (code "68") (name "D+") (class "Default")
      (node (ref "U$1") (pin "D+") (pinfunction "D+_D+") (pintype "bidirectional"))
    )
    (net (code "69") (name "D-") (class "Default")
      (node (ref "U$1") (pin "D-") (pinfunction "D-_D-") (pintype "bidirectional"))
    )
    (net (code "70") (name "DM") (class "Default")
      (node (ref "U$1") (pin "DM") (pinfunction "DM_DM") (pintype "bidirectional"))
    )
    (net (code "71") (name "DP") (class "Default")
      (node (ref "U$1") (pin "DP") (pinfunction "DP_DP") (pintype "bidirectional"))
    )
    (net (code "72") (name "G") (class "Default")
      (node (ref "U$1") (pin "G") (pinfunction "G_G") (pintype "bidirectional"))
    )
    (net (code "73") (name "GND") (class "Default")
      (node (ref "A0") (pin "P$3") (pinfunction "3_P$3") (pintype "passive"))
      (node (ref "A1") (pin "P$3") (pinfunction "3_P$3") (pintype "passive"))
      (node (ref "A10") (pin "P$3") (pinfunction "3_P$3") (pintype "passive"))
      (node (ref "A11") (pin "P$3") (pinfunction "3_P$3") (pintype "passive"))
      (node (ref "A2") (pin "P$3") (pinfunction "3_P$3") (pintype "passive"))
      (node (ref "A3") (pin "P$3") (pinfunction "3_P$3") (pintype "passive"))
      (node (ref "A4") (pin "P$3") (pinfunction "3_P$3") (pintype "passive"))
      (node (ref "A5") (pin "P$3") (pinfunction "3_P$3") (pintype "passive"))
      (node (ref "A6") (pin "P$3") (pinfunction "3_P$3") (pintype "passive"))
      (node (ref "A7") (pin "P$3") (pinfunction "3_P$3") (pintype "passive"))
      (node (ref "A8") (pin "P$3") (pinfunction "3_P$3") (pintype "passive"))
      (node (ref "A9") (pin "P$3") (pinfunction "3_P$3") (pintype "passive"))
      (node (ref "C1") (pin "2") (pinfunction "2_2") (pintype "passive"))
      (node (ref "C16") (pin "2") (pinfunction "2_2") (pintype "passive"))
      (node (ref "C17") (pin "2") (pinfunction "2_2") (pintype "passive"))
      (node (ref "C18") (pin "1") (pinfunction "1_1") (pintype "passive"))
      (node (ref "C2") (pin "2") (pinfunction "2_2") (pintype "passive"))
      (node (ref "C20") (pin "2") (pinfunction "2_2") (pintype "passive"))
      (node (ref "C21") (pin "1") (pinfunction "1_1") (pintype "passive"))
      (node (ref "C3") (pin "2") (pinfunction "2_2") (pintype "passive"))
      (node (ref "C39") (pin "2") (pinfunction "2_2") (pintype "passive"))
      (node (ref "C4") (pin "2") (pinfunction "2_2") (pintype "passive"))
      (node (ref "C40") (pin "2") (pinfunction "2_2") (pintype "passive"))
      (node (ref "C41") (pin "1") (pinfunction "1_1") (pintype "passive"))
      (node (ref "C42") (pin "2") (pinfunction "2_2") (pintype "passive"))
      (node (ref "C43") (pin "1") (pinfunction "1_1") (pintype "passive"))
      (node (ref "C44") (pin "1") (pinfunction "1_1") (pintype "passive"))
      (node (ref "C5") (pin "1") (pinfunction "1_1") (pintype "passive"))
      (node (ref "C54") (pin "2") (pinfunction "2_2") (pintype "passive"))
      (node (ref "C55") (pin "2") (pinfunction "2_2") (pintype "passive"))
      (node (ref "C56") (pin "1") (pinfunction "1_1") (pintype "passive"))
      (node (ref "C57") (pin "2") (pinfunction "2_2") (pintype "passive"))
      (node (ref "C58") (pin "1") (pinfunction "1_1") (pintype "passive"))
      (node (ref "C6") (pin "1") (pinfunction "1_1") (pintype "passive"))
      (node (ref "CS=10") (pin "P$6") (pinfunction "6_P$6") (pintype "passive"))
      (node (ref "CS=11") (pin "P$6") (pinfunction "6_P$6") (pintype "passive"))
      (node (ref "D1") (pin "P$3") (pinfunction "3_P$3") (pintype "passive"))
      (node (ref "D2") (pin "P$3") (pinfunction "3_P$3") (pintype "passive"))
      (node (ref "D3") (pin "P$3") (pinfunction "3_P$3") (pintype "passive"))
      (node (ref "D4") (pin "P$3") (pinfunction "3_P$3") (pintype "passive"))
      (node (ref "D5") (pin "P$3") (pinfunction "3_P$3") (pintype "passive"))
      (node (ref "D6") (pin "P$3") (pinfunction "3_P$3") (pintype "passive"))
      (node (ref "D7") (pin "P$3") (pinfunction "3_P$3") (pintype "passive"))
      (node (ref "D8") (pin "P$3") (pinfunction "3_P$3") (pintype "passive"))
      (node (ref "I2C1") (pin "P$4") (pinfunction "4_P$4") (pintype "passive"))
      (node (ref "I2C2") (pin "P$4") (pinfunction "4_P$4") (pintype "passive"))
      (node (ref "IC7") (pin "11") (pinfunction "AUX_GND_11") (pintype "bidirectional"))
      (node (ref "IC7") (pin "13") (pinfunction "AIN_6GND_13") (pintype "bidirectional"))
      (node (ref "IC7") (pin "15") (pinfunction "AIN_7GND_15") (pintype "bidirectional"))
      (node (ref "IC7") (pin "17") (pinfunction "AIN_0GND_17") (pintype "bidirectional"))
      (node (ref "IC7") (pin "19") (pinfunction "AIN_1GND_19") (pintype "bidirectional"))
      (node (ref "IC7") (pin "20") (pinfunction "AIN2_GND_20") (pintype "bidirectional"))
      (node (ref "IC7") (pin "22") (pinfunction "AIN_3GND_22") (pintype "bidirectional"))
      (node (ref "IC7") (pin "24") (pinfunction "AIN_4GND_24") (pintype "bidirectional"))
      (node (ref "IC7") (pin "26") (pinfunction "AIN_5GND_26") (pintype "bidirectional"))
      (node (ref "IC7") (pin "28") (pinfunction "AGND_2_28") (pintype "bidirectional"))
      (node (ref "IC7") (pin "29") (pinfunction "AGND_3_29") (pintype "bidirectional"))
      (node (ref "IC7") (pin "3") (pinfunction "DAISY_3") (pintype "bidirectional"))
      (node (ref "IC7") (pin "31") (pinfunction "AGND_4_31") (pintype "bidirectional"))
      (node (ref "IC7") (pin "32") (pinfunction "AGND_5_32") (pintype "bidirectional"))
      (node (ref "IC7") (pin "33") (pinfunction "DGND_33") (pintype "bidirectional"))
      (node (ref "IC7") (pin "4") (pinfunction "~{REFSEL}_4") (pintype "bidirectional"))
      (node (ref "IC7") (pin "6") (pinfunction "REFGND_6") (pintype "bidirectional"))
      (node (ref "IC7") (pin "8") (pinfunction "AGND_1_8") (pintype "bidirectional"))
      (node (ref "IC8") (pin "11") (pinfunction "AUX_GND_11") (pintype "bidirectional"))
      (node (ref "IC8") (pin "13") (pinfunction "AIN_6GND_13") (pintype "bidirectional"))
      (node (ref "IC8") (pin "15") (pinfunction "AIN_7GND_15") (pintype "bidirectional"))
      (node (ref "IC8") (pin "17") (pinfunction "AIN_0GND_17") (pintype "bidirectional"))
      (node (ref "IC8") (pin "19") (pinfunction "AIN_1GND_19") (pintype "bidirectional"))
      (node (ref "IC8") (pin "20") (pinfunction "AIN2_GND_20") (pintype "bidirectional"))
      (node (ref "IC8") (pin "22") (pinfunction "AIN_3GND_22") (pintype "bidirectional"))
      (node (ref "IC8") (pin "24") (pinfunction "AIN_4GND_24") (pintype "bidirectional"))
      (node (ref "IC8") (pin "26") (pinfunction "AIN_5GND_26") (pintype "bidirectional"))
      (node (ref "IC8") (pin "28") (pinfunction "AGND_2_28") (pintype "bidirectional"))
      (node (ref "IC8") (pin "29") (pinfunction "AGND_3_29") (pintype "bidirectional"))
      (node (ref "IC8") (pin "3") (pinfunction "DAISY_3") (pintype "bidirectional"))
      (node (ref "IC8") (pin "31") (pinfunction "AGND_4_31") (pintype "bidirectional"))
      (node (ref "IC8") (pin "32") (pinfunction "AGND_5_32") (pintype "bidirectional"))
      (node (ref "IC8") (pin "33") (pinfunction "DGND_33") (pintype "bidirectional"))
      (node (ref "IC8") (pin "4") (pinfunction "~{REFSEL}_4") (pintype "bidirectional"))
      (node (ref "IC8") (pin "6") (pinfunction "REFGND_6") (pintype "bidirectional"))
      (node (ref "IC8") (pin "8") (pinfunction "AGND_1_8") (pintype "bidirectional"))
      (node (ref "IC9") (pin "11") (pinfunction "AUX_GND_11") (pintype "bidirectional"))
      (node (ref "IC9") (pin "13") (pinfunction "AIN_6GND_13") (pintype "bidirectional"))
      (node (ref "IC9") (pin "15") (pinfunction "AIN_7GND_15") (pintype "bidirectional"))
      (node (ref "IC9") (pin "17") (pinfunction "AIN_0GND_17") (pintype "bidirectional"))
      (node (ref "IC9") (pin "19") (pinfunction "AIN_1GND_19") (pintype "bidirectional"))
      (node (ref "IC9") (pin "20") (pinfunction "AIN2_GND_20") (pintype "bidirectional"))
      (node (ref "IC9") (pin "22") (pinfunction "AIN_3GND_22") (pintype "bidirectional"))
      (node (ref "IC9") (pin "24") (pinfunction "AIN_4GND_24") (pintype "bidirectional"))
      (node (ref "IC9") (pin "26") (pinfunction "AIN_5GND_26") (pintype "bidirectional"))
      (node (ref "IC9") (pin "28") (pinfunction "AGND_2_28") (pintype "bidirectional"))
      (node (ref "IC9") (pin "29") (pinfunction "AGND_3_29") (pintype "bidirectional"))
      (node (ref "IC9") (pin "3") (pinfunction "DAISY_3") (pintype "bidirectional"))
      (node (ref "IC9") (pin "31") (pinfunction "AGND_4_31") (pintype "bidirectional"))
      (node (ref "IC9") (pin "32") (pinfunction "AGND_5_32") (pintype "bidirectional"))
      (node (ref "IC9") (pin "33") (pinfunction "DGND_33") (pintype "bidirectional"))
      (node (ref "IC9") (pin "4") (pinfunction "~{REFSEL}_4") (pintype "bidirectional"))
      (node (ref "IC9") (pin "6") (pinfunction "REFGND_6") (pintype "bidirectional"))
      (node (ref "IC9") (pin "8") (pinfunction "AGND_1_8") (pintype "bidirectional"))
      (node (ref "JP10") (pin "15") (pinfunction "15_15") (pintype "passive"))
      (node (ref "JP10") (pin "2") (pinfunction "2_2") (pintype "passive"))
      (node (ref "JP2") (pin "15") (pinfunction "15_15") (pintype "passive"))
      (node (ref "JP2") (pin "2") (pinfunction "2_2") (pintype "passive"))
      (node (ref "JP4") (pin "1") (pinfunction "1_1") (pintype "passive"))
      (node (ref "JP6") (pin "2") (pinfunction "2_2") (pintype "passive"))
      (node (ref "JP7") (pin "1") (pinfunction "1_1") (pintype "passive"))
      (node (ref "LED1") (pin "C") (pinfunction "C_C") (pintype "passive"))
      (node (ref "LED2") (pin "C") (pinfunction "C_C") (pintype "passive"))
      (node (ref "Q1") (pin "1") (pinfunction "S_1") (pintype "bidirectional"))
      (node (ref "Q2") (pin "1") (pinfunction "S_1") (pintype "bidirectional"))
      (node (ref "U$1") (pin "GND1") (pinfunction "GND1_GND1") (pintype "bidirectional"))
      (node (ref "U$1") (pin "GND2") (pinfunction "GND2_GND2") (pintype "bidirectional"))
      (node (ref "U$1") (pin "GND3") (pinfunction "GND3_GND3") (pintype "bidirectional"))
      (node (ref "U$1") (pin "GND6") (pinfunction "GND6_GND6") (pintype "bidirectional"))
      (node (ref "U$2") (pin "NEG") (pinfunction "NEG_NEG") (pintype "bidirectional"))
      (node (ref "U$3") (pin "1") (pinfunction "GND_1") (pintype "input"))
      (node (ref "U$4") (pin "1") (pinfunction "GND_1") (pintype "input"))
      (node (ref "U1") (pin "10") (pinfunction "GND_10") (pintype "power_in"))
    )
    (net (code "74") (name "LED") (class "Default")
      (node (ref "U$1") (pin "LED") (pinfunction "LED_LED") (pintype "bidirectional"))
    )
    (net (code "75") (name "LED1_GND") (class "Default")
      (node (ref "JP3") (pin "2") (pinfunction "2_2") (pintype "passive"))
      (node (ref "Q2") (pin "3") (pinfunction "D_3") (pintype "bidirectional"))
    )
    (net (code "76") (name "LED2_GND") (class "Default")
      (node (ref "JP5") (pin "2") (pinfunction "2_2") (pintype "passive"))
      (node (ref "Q1") (pin "3") (pinfunction "D_3") (pintype "bidirectional"))
    )
    (net (code "77") (name "MISO") (class "Default")
      (node (ref "CS=10") (pin "P$3") (pinfunction "3_P$3") (pintype "passive"))
      (node (ref "CS=11") (pin "P$3") (pinfunction "3_P$3") (pintype "passive"))
      (node (ref "IC7") (pin "36") (pinfunction "SDO_36") (pintype "bidirectional"))
      (node (ref "IC8") (pin "36") (pinfunction "SDO_36") (pintype "bidirectional"))
      (node (ref "IC9") (pin "36") (pinfunction "SDO_36") (pintype "bidirectional"))
      (node (ref "JP1") (pin "14") (pinfunction "14_14") (pintype "passive"))
      (node (ref "JP7") (pin "14") (pinfunction "14_14") (pintype "passive"))
      (node (ref "U$1") (pin "12-MISO/MQSL") (pinfunction "12-MISO/MQSL_12-MISO/MQSL") (pintype "bidirectional"))
    )
    (net (code "78") (name "MOSI") (class "Default")
      (node (ref "CS=10") (pin "P$2") (pinfunction "2_P$2") (pintype "passive"))
      (node (ref "CS=11") (pin "P$2") (pinfunction "2_P$2") (pintype "passive"))
      (node (ref "IC7") (pin "1") (pinfunction "SDI_1") (pintype "bidirectional"))
      (node (ref "IC8") (pin "1") (pinfunction "SDI_1") (pintype "bidirectional"))
      (node (ref "IC9") (pin "1") (pinfunction "SDI_1") (pintype "bidirectional"))
      (node (ref "JP1") (pin "13") (pinfunction "13_13") (pintype "passive"))
      (node (ref "JP7") (pin "13") (pinfunction "13_13") (pintype "passive"))
      (node (ref "U$1") (pin "11-MOSI/CTX1") (pinfunction "11-MOSI/CTX1_11-MOSI/CTX1") (pintype "bidirectional"))
    )
    (net (code "79") (name "NC1") (class "Default")
      (node (ref "IC7") (pin "35") (pinfunction "DNC_35") (pintype "bidirectional"))
    )
    (net (code "80") (name "NC2") (class "Default")
      (node (ref "IC8") (pin "35") (pinfunction "DNC_35") (pintype "bidirectional"))
    )
    (net (code "81") (name "NC3") (class "Default")
      (node (ref "IC9") (pin "35") (pinfunction "DNC_35") (pintype "bidirectional"))
    )
    (net (code "82") (name "Net-(IC7-REFCAP)") (class "Default")
      (node (ref "C18") (pin "2") (pinfunction "2_2") (pintype "passive"))
      (node (ref "C21") (pin "2") (pinfunction "2_2") (pintype "passive"))
      (node (ref "IC7") (pin "7") (pinfunction "REFCAP_7") (pintype "bidirectional"))
    )
    (net (code "83") (name "Net-(IC7-REFIO)") (class "Default")
      (node (ref "C20") (pin "1") (pinfunction "1_1") (pintype "passive"))
      (node (ref "IC7") (pin "5") (pinfunction "REFIO_5") (pintype "bidirectional"))
    )
    (net (code "84") (name "Net-(IC8-REFCAP)") (class "Default")
      (node (ref "C41") (pin "2") (pinfunction "2_2") (pintype "passive"))
      (node (ref "C43") (pin "2") (pinfunction "2_2") (pintype "passive"))
      (node (ref "IC8") (pin "7") (pinfunction "REFCAP_7") (pintype "bidirectional"))
    )
    (net (code "85") (name "Net-(IC8-REFIO)") (class "Default")
      (node (ref "C42") (pin "1") (pinfunction "1_1") (pintype "passive"))
      (node (ref "IC8") (pin "5") (pinfunction "REFIO_5") (pintype "bidirectional"))
    )
    (net (code "86") (name "Net-(IC9-REFCAP)") (class "Default")
      (node (ref "C56") (pin "2") (pinfunction "2_2") (pintype "passive"))
      (node (ref "C58") (pin "2") (pinfunction "2_2") (pintype "passive"))
      (node (ref "IC9") (pin "7") (pinfunction "REFCAP_7") (pintype "bidirectional"))
    )
    (net (code "87") (name "Net-(IC9-REFIO)") (class "Default")
      (node (ref "C57") (pin "1") (pinfunction "1_1") (pintype "passive"))
      (node (ref "IC9") (pin "5") (pinfunction "REFIO_5") (pintype "bidirectional"))
    )
    (net (code "88") (name "Net-(JP3-Pad1)") (class "Default")
      (node (ref "JP3") (pin "1") (pinfunction "1_1") (pintype "passive"))
      (node (ref "R7") (pin "1") (pinfunction "1_1") (pintype "passive"))
    )
    (net (code "89") (name "Net-(JP5-Pad1)") (class "Default")
      (node (ref "JP5") (pin "1") (pinfunction "1_1") (pintype "passive"))
      (node (ref "R8") (pin "1") (pinfunction "1_1") (pintype "passive"))
    )
    (net (code "90") (name "Net-(LED1-PadA)") (class "Default")
      (node (ref "LED1") (pin "A") (pinfunction "A_A") (pintype "passive"))
      (node (ref "R1") (pin "2") (pinfunction "2_2") (pintype "passive"))
    )
    (net (code "91") (name "Net-(LED2-PadA)") (class "Default")
      (node (ref "LED2") (pin "A") (pinfunction "A_A") (pintype "passive"))
      (node (ref "R2") (pin "2") (pinfunction "2_2") (pintype "passive"))
    )
    (net (code "92") (name "PROGRAM") (class "Default")
      (node (ref "U$1") (pin "PROGRAM") (pinfunction "PROGRAM_PROGRAM") (pintype "bidirectional"))
    )
    (net (code "93") (name "R+") (class "Default")
      (node (ref "U$1") (pin "R+") (pinfunction "R+_R+") (pintype "bidirectional"))
    )
    (net (code "94") (name "R-") (class "Default")
      (node (ref "U$1") (pin "R-") (pinfunction "R-_R-") (pintype "bidirectional"))
    )
    (net (code "95") (name "SCK") (class "Default")
      (node (ref "CS=10") (pin "P$4") (pinfunction "4_P$4") (pintype "passive"))
      (node (ref "CS=11") (pin "P$4") (pinfunction "4_P$4") (pintype "passive"))
      (node (ref "IC7") (pin "37") (pinfunction "SCLK_37") (pintype "bidirectional"))
      (node (ref "IC8") (pin "37") (pinfunction "SCLK_37") (pintype "bidirectional"))
      (node (ref "IC9") (pin "37") (pinfunction "SCLK_37") (pintype "bidirectional"))
      (node (ref "JP10") (pin "14") (pinfunction "14_14") (pintype "passive"))
      (node (ref "JP2") (pin "14") (pinfunction "14_14") (pintype "passive"))
      (node (ref "U$1") (pin "13-SCK/LED") (pinfunction "13-SCK/LED_13-SCK/LED") (pintype "bidirectional"))
    )
    (net (code "96") (name "SCL") (class "Default")
      (node (ref "I2C1") (pin "P$3") (pinfunction "3_P$3") (pintype "passive"))
      (node (ref "I2C2") (pin "P$3") (pinfunction "3_P$3") (pintype "passive"))
      (node (ref "JP10") (pin "8") (pinfunction "8_8") (pintype "passive"))
      (node (ref "JP2") (pin "8") (pinfunction "8_8") (pintype "passive"))
      (node (ref "U$1") (pin "19-A5/SCL0") (pinfunction "19-A5/SCL0_19-A5/SCL0") (pintype "bidirectional"))
    )
    (net (code "97") (name "SDA") (class "Default")
      (node (ref "I2C1") (pin "P$2") (pinfunction "2_P$2") (pintype "passive"))
      (node (ref "I2C2") (pin "P$2") (pinfunction "2_P$2") (pintype "passive"))
      (node (ref "JP10") (pin "9") (pinfunction "9_9") (pintype "passive"))
      (node (ref "JP2") (pin "9") (pinfunction "9_9") (pintype "passive"))
      (node (ref "U$1") (pin "18-A4/SDA0") (pinfunction "18-A4/SDA0_18-A4/SDA0") (pintype "bidirectional"))
    )
    (net (code "98") (name "T+") (class "Default")
      (node (ref "U$1") (pin "T+") (pinfunction "T+_T+") (pintype "bidirectional"))
    )
    (net (code "99") (name "T-") (class "Default")
      (node (ref "U$1") (pin "T-") (pinfunction "T-_T-") (pintype "bidirectional"))
    )
    (net (code "100") (name "VBAT") (class "Default")
      (node (ref "U$1") (pin "VBAT") (pinfunction "VBAT_VBAT") (pintype "bidirectional"))
      (node (ref "U$2") (pin "VCC1") (pinfunction "VCC1_VCC1") (pintype "bidirectional"))
      (node (ref "U$2") (pin "VCC2") (pinfunction "VCC2_VCC2") (pintype "bidirectional"))
    )
    (net (code "101") (name "VUSB") (class "Default")
      (node (ref "U$1") (pin "VUSB") (pinfunction "VUSB_VUSB") (pintype "bidirectional"))
    )
    (net (code "102") (name "XBEE_DIN") (class "Default")
      (node (ref "JP7") (pin "3") (pinfunction "3_3") (pintype "passive"))
      (node (ref "U$1") (pin "1-TX1/MISO1/CTX2") (pinfunction "1-TX1/MISO1/CTX2_1-TX1/MISO1/CTX2") (pintype "bidirectional"))
      (node (ref "U1") (pin "3") (pinfunction "DIN/NCONFIG/DIO14_3") (pintype "bidirectional"))
    )
    (net (code "103") (name "XBEE_DOUT") (class "Default")
      (node (ref "JP7") (pin "2") (pinfunction "2_2") (pintype "passive"))
      (node (ref "U$1") (pin "0-RX1/CS1/CRX2") (pinfunction "0-RX1/CS1/CRX2_0-RX1/CS1/CRX2") (pintype "bidirectional"))
      (node (ref "U1") (pin "2") (pinfunction "DOUT/DIO13_2") (pintype "bidirectional"))
    )
    (net (code "104") (name "unconnected-(IC7-AUX_IN-Pad10)") (class "Default")
      (node (ref "IC7") (pin "10") (pinfunction "AUX_IN_10") (pintype "bidirectional"))
    )
    (net (code "105") (name "unconnected-(IC8-AUX_IN-Pad10)") (class "Default")
      (node (ref "IC8") (pin "10") (pinfunction "AUX_IN_10") (pintype "bidirectional"))
    )
    (net (code "106") (name "unconnected-(IC9-AUX_IN-Pad10)") (class "Default")
      (node (ref "IC9") (pin "10") (pinfunction "AUX_IN_10") (pintype "bidirectional"))
    )
    (net (code "107") (name "unconnected-(U$1-PadGND4)") (class "Default")
      (node (ref "U$1") (pin "GND4") (pinfunction "GND4_GND4") (pintype "bidirectional"))
    )
    (net (code "108") (name "unconnected-(U$1-PadGND5)") (class "Default")
      (node (ref "U$1") (pin "GND5") (pinfunction "GND5_GND5") (pintype "bidirectional"))
    )
    (net (code "109") (name "unconnected-(U$1-PadON{slash}OFF)") (class "Default")
      (node (ref "U$1") (pin "ON/OFF") (pinfunction "ON/OFF_ON/OFF") (pintype "bidirectional"))
    )
    (net (code "110") (name "unconnected-(U1-AD0{slash}DIO0-Pad20)") (class "Default")
      (node (ref "U1") (pin "20") (pinfunction "AD0/DIO0_20") (pintype "bidirectional"))
    )
    (net (code "111") (name "unconnected-(U1-AD1{slash}DIO1{slash}SPI_NATTN-Pad19)") (class "Default")
      (node (ref "U1") (pin "19") (pinfunction "AD1/DIO1/SPI_NATTN_19") (pintype "bidirectional"))
    )
    (net (code "112") (name "unconnected-(U1-AD2{slash}DIO2{slash}SPI_CLK-Pad18)") (class "Default")
      (node (ref "U1") (pin "18") (pinfunction "AD2/DIO2/SPI_CLK_18") (pintype "bidirectional"))
    )
    (net (code "113") (name "unconnected-(U1-AD3{slash}DIO3{slash}SPI_NSSEL-Pad17)") (class "Default")
      (node (ref "U1") (pin "17") (pinfunction "AD3/DIO3/SPI_NSSEL_17") (pintype "bidirectional"))
    )
    (net (code "114") (name "unconnected-(U1-ASSOCIATE{slash}DIO5-Pad15)") (class "Default")
      (node (ref "U1") (pin "15") (pinfunction "ASSOCIATE/DIO5_15") (pintype "output"))
    )
    (net (code "115") (name "unconnected-(U1-DIO4{slash}SPI_MOSI-Pad11)") (class "Default")
      (node (ref "U1") (pin "11") (pinfunction "DIO4/SPI_MOSI_11") (pintype "bidirectional"))
    )
    (net (code "116") (name "unconnected-(U1-DIO10{slash}PWM0-Pad6)") (class "Default")
      (node (ref "U1") (pin "6") (pinfunction "DIO10/PWM0_6") (pintype "bidirectional"))
    )
    (net (code "117") (name "unconnected-(U1-DIO11{slash}PWM1-Pad7)") (class "Default")
      (node (ref "U1") (pin "7") (pinfunction "DIO11/PWM1_7") (pintype "bidirectional"))
    )
    (net (code "118") (name "unconnected-(U1-DIO12{slash}SPI_MISO-Pad4)") (class "Default")
      (node (ref "U1") (pin "4") (pinfunction "DIO12/SPI_MISO_4") (pintype "bidirectional"))
    )
    (net (code "119") (name "unconnected-(U1-NCTS{slash}DIO7-Pad12)") (class "Default")
      (node (ref "U1") (pin "12") (pinfunction "NCTS/DIO7_12") (pintype "bidirectional"))
    )
    (net (code "120") (name "unconnected-(U1-NDTR{slash}SLEEP_RQ{slash}DIO8-Pad9)") (class "Default")
      (node (ref "U1") (pin "9") (pinfunction "NDTR/SLEEP_RQ/DIO8_9") (pintype "bidirectional"))
    )
    (net (code "121") (name "unconnected-(U1-NRTS{slash}DIO6-Pad16)") (class "Default")
      (node (ref "U1") (pin "16") (pinfunction "NRTS/DIO6_16") (pintype "input"))
    )
    (net (code "122") (name "unconnected-(U1-ON_NSLEEP{slash}DIO9-Pad13)") (class "Default")
      (node (ref "U1") (pin "13") (pinfunction "ON_NSLEEP/DIO9_13") (pintype "bidirectional"))
    )
    (net (code "123") (name "unconnected-(U1-VREF-Pad14)") (class "Default")
      (node (ref "U1") (pin "14") (pinfunction "VREF_14") (pintype "input"))
    )
    (net (code "124") (name "unconnected-(U1-~{RESET}-Pad5)") (class "Default")
      (node (ref "U1") (pin "5") (pinfunction "~{RESET}_5") (pintype "input"))
    )
  )
)
